# 2_STM32L4.net
KiCad netlist of a schematic drawn in Altium Designer
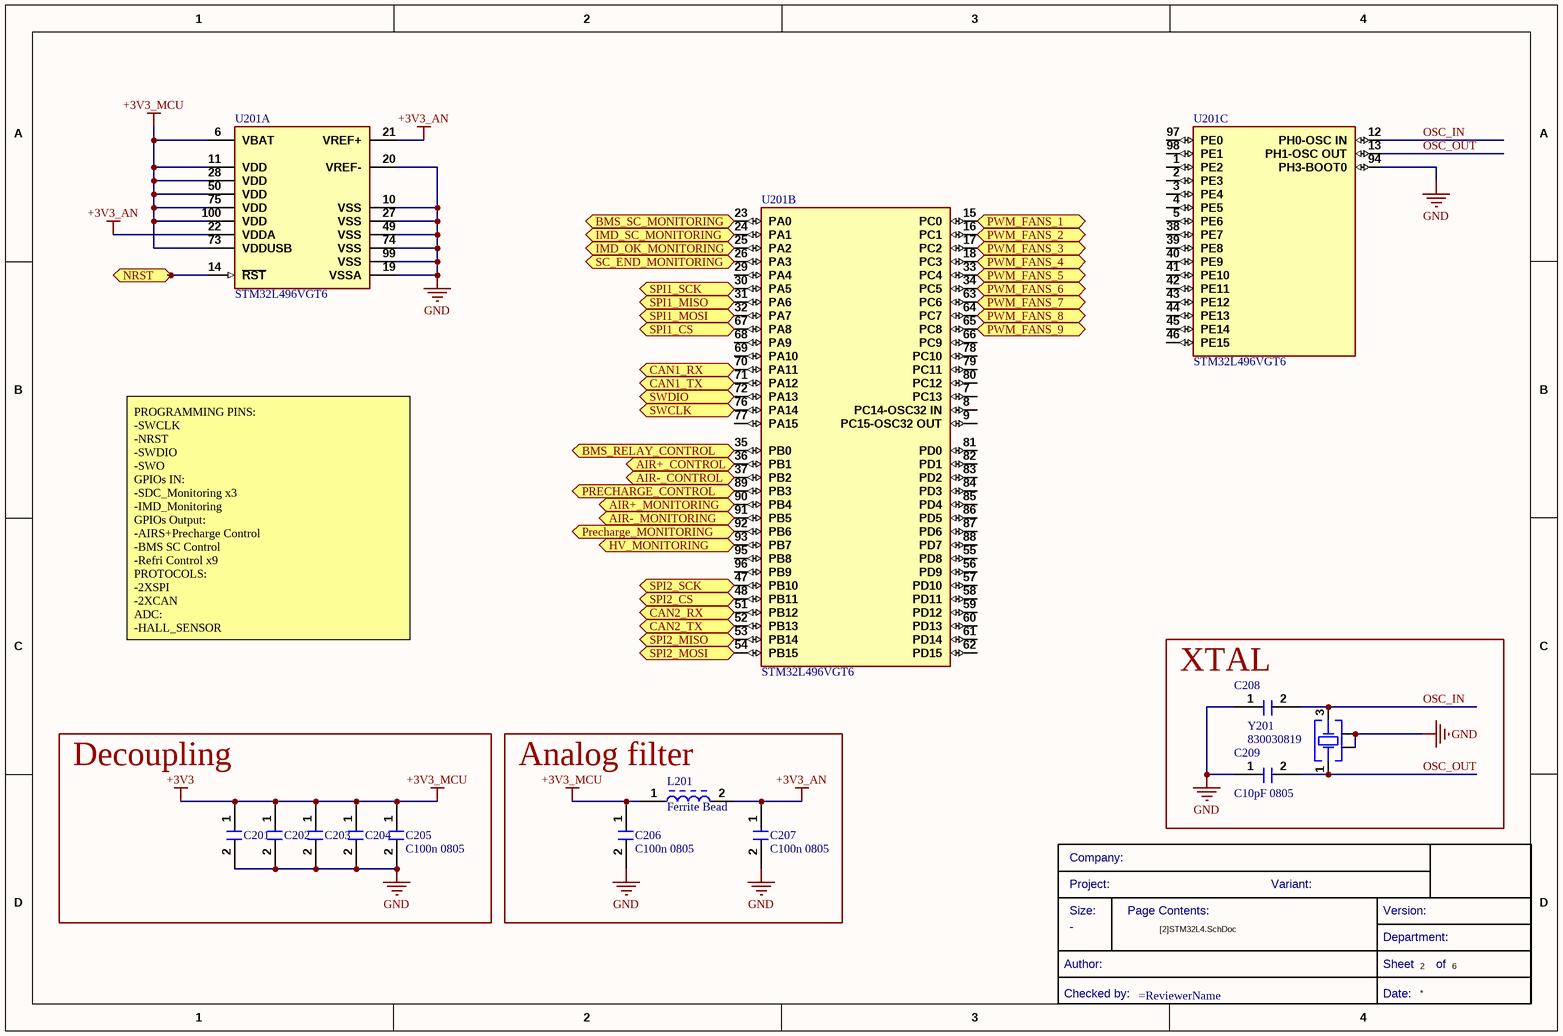
[diagram p0: [2]STM32L4.SchDoc]

(export (version "E")
  (design (tool "Eeschema 10.0.6"))
  (components
    (comp (ref "C201")
      (value "C100n 0805")
      (footprint "C0805FNPC-R")
      (description "Cap, 0.1ΜF, 50V, 10%, X7R, 0805")
      (fields (field (name "TOLERANCE") "10%") (field (name ".CREATOR") "DR"))
      (libsource (lib "EMEA- E-Tech Racing- I'Escola d'Enginyeria de Barcelona Est") (part "C100p-50V-0805FNPC-C0G/NP0"))
    )
    (comp (ref "C202")
      (value "C100n 0805")
      (footprint "C0805FNPC-R")
      (description "Cap, 0.1ΜF, 50V, 10%, X7R, 0805")
      (fields (field (name "TOLERANCE") "10%") (field (name ".CREATOR") "DR"))
      (libsource (lib "EMEA- E-Tech Racing- I'Escola d'Enginyeria de Barcelona Est") (part "C100p-50V-0805FNPC-C0G/NP0"))
    )
    (comp (ref "C203")
      (value "C100n 0805")
      (footprint "C0805FNPC-R")
      (description "Cap, 0.1ΜF, 50V, 10%, X7R, 0805")
      (fields (field (name "TOLERANCE") "10%") (field (name ".CREATOR") "DR"))
      (libsource (lib "EMEA- E-Tech Racing- I'Escola d'Enginyeria de Barcelona Est") (part "C100p-50V-0805FNPC-C0G/NP0"))
    )
    (comp (ref "C204")
      (value "C100n 0805")
      (footprint "C0805FNPC-R")
      (description "Cap, 0.1ΜF, 50V, 10%, X7R, 0805")
      (fields (field (name "TOLERANCE") "10%") (field (name ".CREATOR") "DR"))
      (libsource (lib "EMEA- E-Tech Racing- I'Escola d'Enginyeria de Barcelona Est") (part "C100p-50V-0805FNPC-C0G/NP0"))
    )
    (comp (ref "C205")
      (value "C100n 0805")
      (footprint "C0805FNPC-R")
      (description "Cap, 0.1ΜF, 50V, 10%, X7R, 0805")
      (fields (field (name "TOLERANCE") "10%") (field (name ".CREATOR") "DR"))
      (libsource (lib "EMEA- E-Tech Racing- I'Escola d'Enginyeria de Barcelona Est") (part "C100p-50V-0805FNPC-C0G/NP0"))
    )
    (comp (ref "C206")
      (value "C100n 0805")
      (footprint "C0805FNPC-R")
      (description "Cap, 0.1ΜF, 50V, 10%, X7R, 0805")
      (fields (field (name "TOLERANCE") "10%") (field (name ".CREATOR") "DR"))
      (libsource (lib "EMEA- E-Tech Racing- I'Escola d'Enginyeria de Barcelona Est") (part "C100p-50V-0805FNPC-C0G/NP0"))
    )
    (comp (ref "C207")
      (value "C100n 0805")
      (footprint "C0805FNPC-R")
      (description "Cap, 0.1ΜF, 50V, 10%, X7R, 0805")
      (fields (field (name "TOLERANCE") "10%") (field (name ".CREATOR") "DR"))
      (libsource (lib "EMEA- E-Tech Racing- I'Escola d'Enginyeria de Barcelona Est") (part "C100p-50V-0805FNPC-C0G/NP0"))
    )
    (comp (ref "C208")
      (value "C10pF 0805")
      (footprint "WCAP-CSGP_0805_L2W1.25H0.6_Reflow")
      (libsource (lib "EMEA- E-Tech Racing- I'Escola d'Enginyeria de Barcelona Est") (part "C100p-50V-0805FNPC-C0G/NP0"))
    )
    (comp (ref "C209")
      (value "C10pF 0805")
      (footprint "WCAP-CSGP_0805_L2W1.25H0.6_Reflow")
      (libsource (lib "EMEA- E-Tech Racing- I'Escola d'Enginyeria de Barcelona Est") (part "C100p-50V-0805FNPC-C0G/NP0"))
    )
    (comp (ref "L201")
      (value "Ferrite Bead")
      (footprint "L_Ferrite_bead_0805")
      (fields
        (field (name "TOLERANCE") "25%")
        (field (name "MANUFACTURER PART NUMBER") "BLM18EG331TN1D")
        (field (name "MANUFACTURER") "Murata")
        (field (name ".CREATOR") "GP")
      )
      (libsource (lib "EMEA- E-Tech Racing- I'Escola d'Enginyeria de Barcelona Est") (part "L_Ferrite_bead_782853561"))
    )
    (comp (ref "U201")
      (value "STM32L496VGT6")
      (footprint "FP-LQFP100-1L-IPC_A")
      (description "RISC Microcontroller, 32-Bit, FLASH, CORTEX-M4 CPU, 80MHz, CMOS, PQFP100")
      (libsource (lib "EMEA- E-Tech Racing- I'Escola d'Enginyeria de Barcelona Est") (part "c3654b0af0513536dfc3423c68ccd0e"))
    )
    (comp (ref "Y201")
      (value "830030819")
      (footprint "WE-XTAL_CFPX-104")
      (description "WE-XTAL Quartz Crystal, SMT, CFPX-104, 16MHz, +/-50ppm")
      (fields (field (name "MANUFACTURER") "Wurth Elektronik"))
      (libsource (lib "EMEA- E-Tech Racing- I'Escola d'Enginyeria de Barcelona Est") (part "830030819"))
    )
  )
  (nets
    (net (code "1") (name "+3V3") (class "Default")
      (node (ref "C201") (pin "1") (pinfunction "1_1") (pintype "passive"))
      (node (ref "C202") (pin "1") (pinfunction "1_1") (pintype "passive"))
      (node (ref "C203") (pin "1") (pinfunction "1_1") (pintype "passive"))
      (node (ref "C204") (pin "1") (pinfunction "1_1") (pintype "passive"))
      (node (ref "C205") (pin "1") (pinfunction "1_1") (pintype "passive"))
      (node (ref "C206") (pin "1") (pinfunction "1_1") (pintype "passive"))
      (node (ref "L201") (pin "1") (pinfunction "1_1") (pintype "passive"))
      (node (ref "U201") (pin "100") (pinfunction "VDD_100") (pintype "power_in"))
      (node (ref "U201") (pin "11") (pinfunction "VDD_11") (pintype "power_in"))
      (node (ref "U201") (pin "28") (pinfunction "VDD_28") (pintype "power_in"))
      (node (ref "U201") (pin "50") (pinfunction "VDD_50") (pintype "power_in"))
      (node (ref "U201") (pin "6") (pinfunction "VBAT_6") (pintype "power_in"))
      (node (ref "U201") (pin "73") (pinfunction "VDDUSB_73") (pintype "power_in"))
      (node (ref "U201") (pin "75") (pinfunction "VDD_75") (pintype "power_in"))
    )
    (net (code "2") (name "+3V3_AN") (class "Default")
      (node (ref "C207") (pin "1") (pinfunction "1_1") (pintype "passive"))
      (node (ref "L201") (pin "2") (pinfunction "2_2") (pintype "passive"))
      (node (ref "U201") (pin "21") (pinfunction "VREF+_21") (pintype "power_in"))
      (node (ref "U201") (pin "22") (pinfunction "VDDA_22") (pintype "power_in"))
    )
    (net (code "3") (name "/AIR+_CONTROL") (class "Default")
      (node (ref "U201") (pin "36") (pinfunction "PB1_36") (pintype "bidirectional"))
    )
    (net (code "4") (name "/AIR+_MONITORING") (class "Default")
      (node (ref "U201") (pin "90") (pinfunction "PB4_90") (pintype "bidirectional"))
    )
    (net (code "5") (name "/AIR-_CONTROL") (class "Default")
      (node (ref "U201") (pin "37") (pinfunction "PB2_37") (pintype "bidirectional"))
    )
    (net (code "6") (name "/AIR-_MONITORING") (class "Default")
      (node (ref "U201") (pin "91") (pinfunction "PB5_91") (pintype "bidirectional"))
    )
    (net (code "7") (name "/BMS_RELAY_CONTROL") (class "Default")
      (node (ref "U201") (pin "35") (pinfunction "PB0_35") (pintype "bidirectional"))
    )
    (net (code "8") (name "/BMS_SC_MONITORING") (class "Default")
      (node (ref "U201") (pin "23") (pinfunction "PA0_23") (pintype "bidirectional"))
    )
    (net (code "9") (name "/CAN1_RX") (class "Default")
      (node (ref "U201") (pin "70") (pinfunction "PA11_70") (pintype "bidirectional"))
    )
    (net (code "10") (name "/CAN1_TX") (class "Default")
      (node (ref "U201") (pin "71") (pinfunction "PA12_71") (pintype "bidirectional"))
    )
    (net (code "11") (name "/CAN2_RX") (class "Default")
      (node (ref "U201") (pin "51") (pinfunction "PB12_51") (pintype "bidirectional"))
    )
    (net (code "12") (name "/CAN2_TX") (class "Default")
      (node (ref "U201") (pin "52") (pinfunction "PB13_52") (pintype "bidirectional"))
    )
    (net (code "13") (name "/HV_MONITORING") (class "Default")
      (node (ref "U201") (pin "93") (pinfunction "PB7_93") (pintype "bidirectional"))
    )
    (net (code "14") (name "/IMD_OK_MONITORING") (class "Default")
      (node (ref "U201") (pin "25") (pinfunction "PA2_25") (pintype "bidirectional"))
    )
    (net (code "15") (name "/IMD_SC_MONITORING") (class "Default")
      (node (ref "U201") (pin "24") (pinfunction "PA1_24") (pintype "bidirectional"))
    )
    (net (code "16") (name "/NRST") (class "Default")
      (node (ref "U201") (pin "14") (pinfunction "~{RST}_14") (pintype "input"))
    )
    (net (code "17") (name "/OSC_IN") (class "Default")
      (node (ref "C208") (pin "2") (pinfunction "2_2") (pintype "passive"))
      (node (ref "U201") (pin "12") (pinfunction "PH0-OSC_IN_12") (pintype "bidirectional"))
      (node (ref "Y201") (pin "3") (pinfunction "Crystal_3") (pintype "passive"))
    )
    (net (code "18") (name "/OSC_OUT") (class "Default")
      (node (ref "C209") (pin "2") (pinfunction "2_2") (pintype "passive"))
      (node (ref "U201") (pin "13") (pinfunction "PH1-OSC_OUT_13") (pintype "bidirectional"))
      (node (ref "Y201") (pin "1") (pinfunction "Crystal_1") (pintype "passive"))
    )
    (net (code "19") (name "/PRECHARGE_CONTROL") (class "Default")
      (node (ref "U201") (pin "89") (pinfunction "PB3_89") (pintype "bidirectional"))
    )
    (net (code "20") (name "/PWM_FANS_1") (class "Default")
      (node (ref "U201") (pin "15") (pinfunction "PC0_15") (pintype "bidirectional"))
    )
    (net (code "21") (name "/PWM_FANS_2") (class "Default")
      (node (ref "U201") (pin "16") (pinfunction "PC1_16") (pintype "bidirectional"))
    )
    (net (code "22") (name "/PWM_FANS_3") (class "Default")
      (node (ref "U201") (pin "17") (pinfunction "PC2_17") (pintype "bidirectional"))
    )
    (net (code "23") (name "/PWM_FANS_4") (class "Default")
      (node (ref "U201") (pin "18") (pinfunction "PC3_18") (pintype "bidirectional"))
    )
    (net (code "24") (name "/PWM_FANS_5") (class "Default")
      (node (ref "U201") (pin "33") (pinfunction "PC4_33") (pintype "bidirectional"))
    )
    (net (code "25") (name "/PWM_FANS_6") (class "Default")
      (node (ref "U201") (pin "34") (pinfunction "PC5_34") (pintype "bidirectional"))
    )
    (net (code "26") (name "/PWM_FANS_7") (class "Default")
      (node (ref "U201") (pin "63") (pinfunction "PC6_63") (pintype "bidirectional"))
    )
    (net (code "27") (name "/PWM_FANS_8") (class "Default")
      (node (ref "U201") (pin "64") (pinfunction "PC7_64") (pintype "bidirectional"))
    )
    (net (code "28") (name "/PWM_FANS_9") (class "Default")
      (node (ref "U201") (pin "65") (pinfunction "PC8_65") (pintype "bidirectional"))
    )
    (net (code "29") (name "/Precharge_MONITORING") (class "Default")
      (node (ref "U201") (pin "92") (pinfunction "PB6_92") (pintype "bidirectional"))
    )
    (net (code "30") (name "/SC_END_MONITORING") (class "Default")
      (node (ref "U201") (pin "26") (pinfunction "PA3_26") (pintype "bidirectional"))
    )
    (net (code "31") (name "/SPI1_CS") (class "Default")
      (node (ref "U201") (pin "67") (pinfunction "PA8_67") (pintype "bidirectional"))
    )
    (net (code "32") (name "/SPI1_MISO") (class "Default")
      (node (ref "U201") (pin "31") (pinfunction "PA6_31") (pintype "bidirectional"))
    )
    (net (code "33") (name "/SPI1_MOSI") (class "Default")
      (node (ref "U201") (pin "32") (pinfunction "PA7_32") (pintype "bidirectional"))
    )
    (net (code "34") (name "/SPI1_SCK") (class "Default")
      (node (ref "U201") (pin "30") (pinfunction "PA5_30") (pintype "bidirectional"))
    )
    (net (code "35") (name "/SPI2_CS") (class "Default")
      (node (ref "U201") (pin "48") (pinfunction "PB11_48") (pintype "bidirectional"))
    )
    (net (code "36") (name "/SPI2_MISO") (class "Default")
      (node (ref "U201") (pin "53") (pinfunction "PB14_53") (pintype "bidirectional"))
    )
    (net (code "37") (name "/SPI2_MOSI") (class "Default")
      (node (ref "U201") (pin "54") (pinfunction "PB15_54") (pintype "bidirectional"))
    )
    (net (code "38") (name "/SPI2_SCK") (class "Default")
      (node (ref "U201") (pin "47") (pinfunction "PB10_47") (pintype "bidirectional"))
    )
    (net (code "39") (name "/SWCLK") (class "Default")
      (node (ref "U201") (pin "76") (pinfunction "PA14_76") (pintype "bidirectional"))
    )
    (net (code "40") (name "/SWDIO") (class "Default")
      (node (ref "U201") (pin "72") (pinfunction "PA13_72") (pintype "bidirectional"))
    )
    (net (code "41") (name "GND") (class "Default")
      (node (ref "C201") (pin "2") (pinfunction "2_2") (pintype "passive"))
      (node (ref "C202") (pin "2") (pinfunction "2_2") (pintype "passive"))
      (node (ref "C203") (pin "2") (pinfunction "2_2") (pintype "passive"))
      (node (ref "C204") (pin "2") (pinfunction "2_2") (pintype "passive"))
      (node (ref "C205") (pin "2") (pinfunction "2_2") (pintype "passive"))
      (node (ref "C206") (pin "2") (pinfunction "2_2") (pintype "passive"))
      (node (ref "C207") (pin "2") (pinfunction "2_2") (pintype "passive"))
      (node (ref "C208") (pin "1") (pinfunction "1_1") (pintype "passive"))
      (node (ref "C209") (pin "1") (pinfunction "1_1") (pintype "passive"))
      (node (ref "U201") (pin "10") (pinfunction "VSS_10") (pintype "power_in"))
      (node (ref "U201") (pin "19") (pinfunction "VSSA_19") (pintype "power_in"))
      (node (ref "U201") (pin "20") (pinfunction "VREF-_20") (pintype "power_in"))
      (node (ref "U201") (pin "27") (pinfunction "VSS_27") (pintype "power_in"))
      (node (ref "U201") (pin "49") (pinfunction "VSS_49") (pintype "power_in"))
      (node (ref "U201") (pin "74") (pinfunction "VSS_74") (pintype "power_in"))
      (node (ref "U201") (pin "94") (pinfunction "PH3-BOOT0_94") (pintype "bidirectional"))
      (node (ref "U201") (pin "99") (pinfunction "VSS_99") (pintype "power_in"))
      (node (ref "Y201") (pin "2") (pinfunction "GND_&_Lid_2") (pintype "passive"))
      (node (ref "Y201") (pin "4") (pinfunction "GND_&_Lid_4") (pintype "passive"))
    )
    (net (code "42") (name "unconnected-(U201B-PA4-Pad29)") (class "Default")
      (node (ref "U201") (pin "29") (pinfunction "PA4_29") (pintype "bidirectional"))
    )
    (net (code "43") (name "unconnected-(U201B-PA9-Pad68)") (class "Default")
      (node (ref "U201") (pin "68") (pinfunction "PA9_68") (pintype "bidirectional"))
    )
    (net (code "44") (name "unconnected-(U201B-PA10-Pad69)") (class "Default")
      (node (ref "U201") (pin "69") (pinfunction "PA10_69") (pintype "bidirectional"))
    )
    (net (code "45") (name "unconnected-(U201B-PA15-Pad77)") (class "Default")
      (node (ref "U201") (pin "77") (pinfunction "PA15_77") (pintype "bidirectional"))
    )
    (net (code "46") (name "unconnected-(U201B-PB8-Pad95)") (class "Default")
      (node (ref "U201") (pin "95") (pinfunction "PB8_95") (pintype "bidirectional"))
    )
    (net (code "47") (name "unconnected-(U201B-PB9-Pad96)") (class "Default")
      (node (ref "U201") (pin "96") (pinfunction "PB9_96") (pintype "bidirectional"))
    )
    (net (code "48") (name "unconnected-(U201B-PC9-Pad66)") (class "Default")
      (node (ref "U201") (pin "66") (pinfunction "PC9_66") (pintype "bidirectional"))
    )
    (net (code "49") (name "unconnected-(U201B-PC10-Pad78)") (class "Default")
      (node (ref "U201") (pin "78") (pinfunction "PC10_78") (pintype "bidirectional"))
    )
    (net (code "50") (name "unconnected-(U201B-PC11-Pad79)") (class "Default")
      (node (ref "U201") (pin "79") (pinfunction "PC11_79") (pintype "bidirectional"))
    )
    (net (code "51") (name "unconnected-(U201B-PC12-Pad80)") (class "Default")
      (node (ref "U201") (pin "80") (pinfunction "PC12_80") (pintype "bidirectional"))
    )
    (net (code "52") (name "unconnected-(U201B-PC13-Pad7)") (class "Default")
      (node (ref "U201") (pin "7") (pinfunction "PC13_7") (pintype "bidirectional"))
    )
    (net (code "53") (name "unconnected-(U201B-PC14-OSC32_IN-Pad8)") (class "Default")
      (node (ref "U201") (pin "8") (pinfunction "PC14-OSC32_IN_8") (pintype "bidirectional"))
    )
    (net (code "54") (name "unconnected-(U201B-PC15-OSC32_OUT-Pad9)") (class "Default")
      (node (ref "U201") (pin "9") (pinfunction "PC15-OSC32_OUT_9") (pintype "bidirectional"))
    )
    (net (code "55") (name "unconnected-(U201B-PD0-Pad81)") (class "Default")
      (node (ref "U201") (pin "81") (pinfunction "PD0_81") (pintype "bidirectional"))
    )
    (net (code "56") (name "unconnected-(U201B-PD1-Pad82)") (class "Default")
      (node (ref "U201") (pin "82") (pinfunction "PD1_82") (pintype "bidirectional"))
    )
    (net (code "57") (name "unconnected-(U201B-PD2-Pad83)") (class "Default")
      (node (ref "U201") (pin "83") (pinfunction "PD2_83") (pintype "bidirectional"))
    )
    (net (code "58") (name "unconnected-(U201B-PD3-Pad84)") (class "Default")
      (node (ref "U201") (pin "84") (pinfunction "PD3_84") (pintype "bidirectional"))
    )
    (net (code "59") (name "unconnected-(U201B-PD4-Pad85)") (class "Default")
      (node (ref "U201") (pin "85") (pinfunction "PD4_85") (pintype "bidirectional"))
    )
    (net (code "60") (name "unconnected-(U201B-PD5-Pad86)") (class "Default")
      (node (ref "U201") (pin "86") (pinfunction "PD5_86") (pintype "bidirectional"))
    )
    (net (code "61") (name "unconnected-(U201B-PD6-Pad87)") (class "Default")
      (node (ref "U201") (pin "87") (pinfunction "PD6_87") (pintype "bidirectional"))
    )
    (net (code "62") (name "unconnected-(U201B-PD7-Pad88)") (class "Default")
      (node (ref "U201") (pin "88") (pinfunction "PD7_88") (pintype "bidirectional"))
    )
    (net (code "63") (name "unconnected-(U201B-PD8-Pad55)") (class "Default")
      (node (ref "U201") (pin "55") (pinfunction "PD8_55") (pintype "bidirectional"))
    )
    (net (code "64") (name "unconnected-(U201B-PD9-Pad56)") (class "Default")
      (node (ref "U201") (pin "56") (pinfunction "PD9_56") (pintype "bidirectional"))
    )
    (net (code "65") (name "unconnected-(U201B-PD10-Pad57)") (class "Default")
      (node (ref "U201") (pin "57") (pinfunction "PD10_57") (pintype "bidirectional"))
    )
    (net (code "66") (name "unconnected-(U201B-PD11-Pad58)") (class "Default")
      (node (ref "U201") (pin "58") (pinfunction "PD11_58") (pintype "bidirectional"))
    )
    (net (code "67") (name "unconnected-(U201B-PD12-Pad59)") (class "Default")
      (node (ref "U201") (pin "59") (pinfunction "PD12_59") (pintype "bidirectional"))
    )
    (net (code "68") (name "unconnected-(U201B-PD13-Pad60)") (class "Default")
      (node (ref "U201") (pin "60") (pinfunction "PD13_60") (pintype "bidirectional"))
    )
    (net (code "69") (name "unconnected-(U201B-PD14-Pad61)") (class "Default")
      (node (ref "U201") (pin "61") (pinfunction "PD14_61") (pintype "bidirectional"))
    )
    (net (code "70") (name "unconnected-(U201B-PD15-Pad62)") (class "Default")
      (node (ref "U201") (pin "62") (pinfunction "PD15_62") (pintype "bidirectional"))
    )
    (net (code "71") (name "unconnected-(U201C-PE0-Pad97)") (class "Default")
      (node (ref "U201") (pin "97") (pinfunction "PE0_97") (pintype "bidirectional"))
    )
    (net (code "72") (name "unconnected-(U201C-PE1-Pad98)") (class "Default")
      (node (ref "U201") (pin "98") (pinfunction "PE1_98") (pintype "bidirectional"))
    )
    (net (code "73") (name "unconnected-(U201C-PE2-Pad1)") (class "Default")
      (node (ref "U201") (pin "1") (pinfunction "PE2_1") (pintype "bidirectional"))
    )
    (net (code "74") (name "unconnected-(U201C-PE3-Pad2)") (class "Default")
      (node (ref "U201") (pin "2") (pinfunction "PE3_2") (pintype "bidirectional"))
    )
    (net (code "75") (name "unconnected-(U201C-PE4-Pad3)") (class "Default")
      (node (ref "U201") (pin "3") (pinfunction "PE4_3") (pintype "bidirectional"))
    )
    (net (code "76") (name "unconnected-(U201C-PE5-Pad4)") (class "Default")
      (node (ref "U201") (pin "4") (pinfunction "PE5_4") (pintype "bidirectional"))
    )
    (net (code "77") (name "unconnected-(U201C-PE6-Pad5)") (class "Default")
      (node (ref "U201") (pin "5") (pinfunction "PE6_5") (pintype "bidirectional"))
    )
    (net (code "78") (name "unconnected-(U201C-PE7-Pad38)") (class "Default")
      (node (ref "U201") (pin "38") (pinfunction "PE7_38") (pintype "bidirectional"))
    )
    (net (code "79") (name "unconnected-(U201C-PE8-Pad39)") (class "Default")
      (node (ref "U201") (pin "39") (pinfunction "PE8_39") (pintype "bidirectional"))
    )
    (net (code "80") (name "unconnected-(U201C-PE9-Pad40)") (class "Default")
      (node (ref "U201") (pin "40") (pinfunction "PE9_40") (pintype "bidirectional"))
    )
    (net (code "81") (name "unconnected-(U201C-PE10-Pad41)") (class "Default")
      (node (ref "U201") (pin "41") (pinfunction "PE10_41") (pintype "bidirectional"))
    )
    (net (code "82") (name "unconnected-(U201C-PE11-Pad42)") (class "Default")
      (node (ref "U201") (pin "42") (pinfunction "PE11_42") (pintype "bidirectional"))
    )
    (net (code "83") (name "unconnected-(U201C-PE12-Pad43)") (class "Default")
      (node (ref "U201") (pin "43") (pinfunction "PE12_43") (pintype "bidirectional"))
    )
    (net (code "84") (name "unconnected-(U201C-PE13-Pad44)") (class "Default")
      (node (ref "U201") (pin "44") (pinfunction "PE13_44") (pintype "bidirectional"))
    )
    (net (code "85") (name "unconnected-(U201C-PE14-Pad45)") (class "Default")
      (node (ref "U201") (pin "45") (pinfunction "PE14_45") (pintype "bidirectional"))
    )
    (net (code "86") (name "unconnected-(U201C-PE15-Pad46)") (class "Default")
      (node (ref "U201") (pin "46") (pinfunction "PE15_46") (pintype "bidirectional"))
    )
  )
)
